# FPGA.net
KiCad netlist of a schematic drawn in Altium Designer
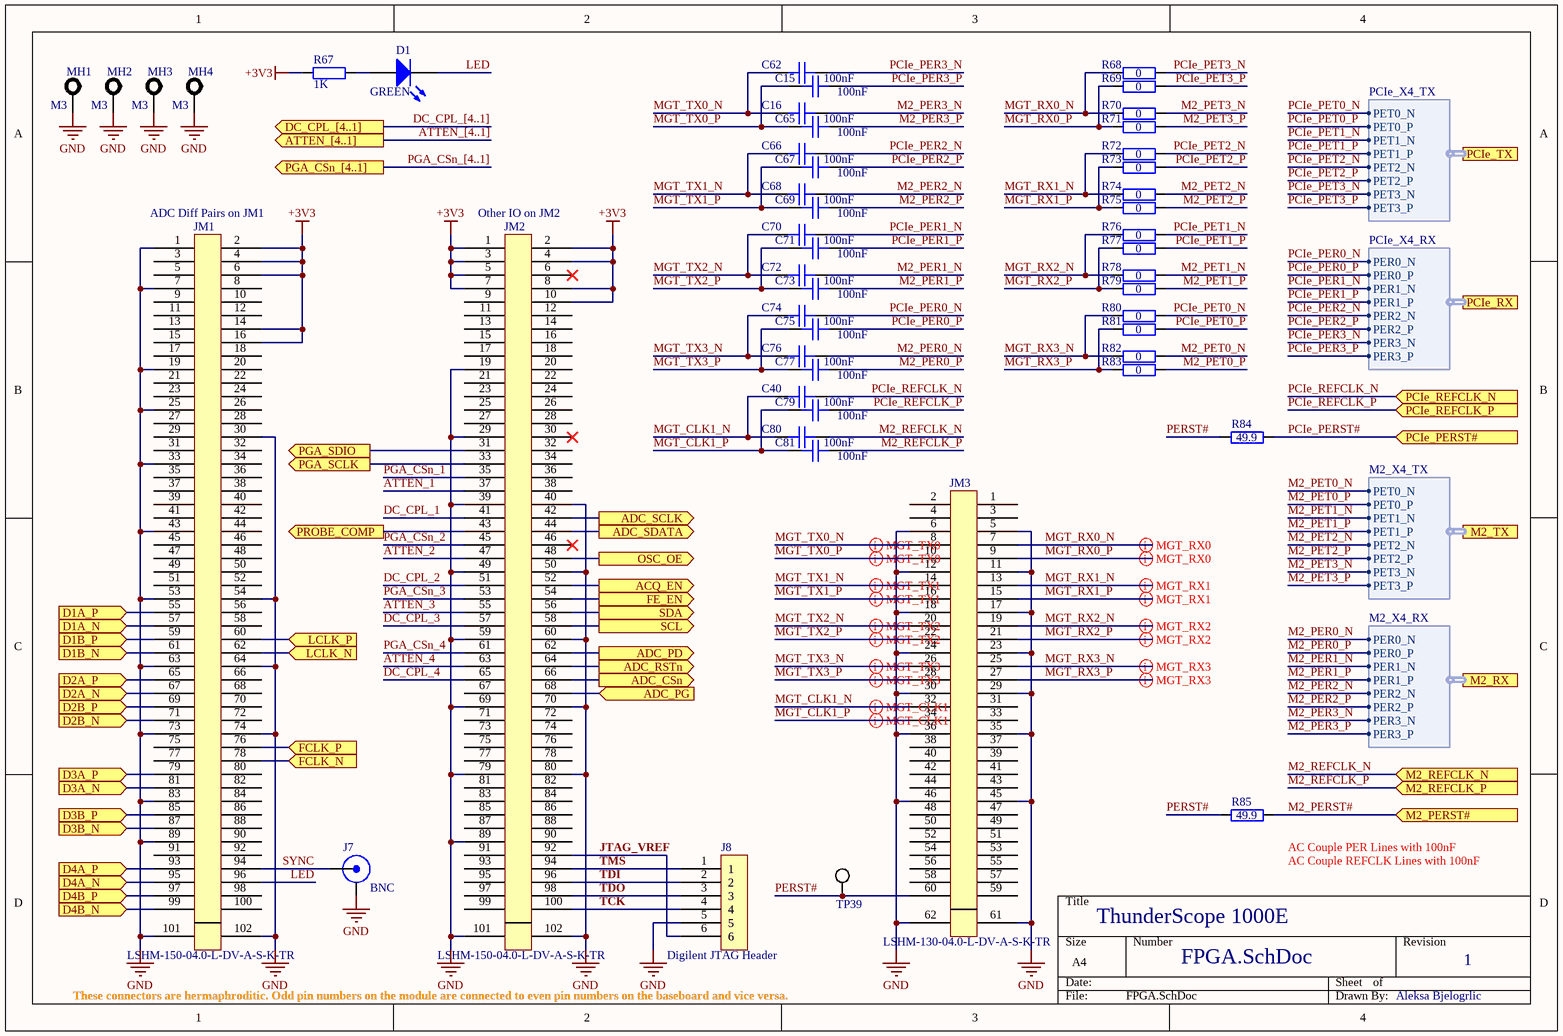
[diagram p0: FPGA.SchDoc]

(export (version "E")
  (design (tool "Eeschema 10.0.6"))
  (components
    (comp (ref "C15")
      (value "100nF")
      (footprint "GEN_C_0201")
      (libsource (lib "DSO") (part "CAP 100nF 6.3V X5R 0201"))
    )
    (comp (ref "C16")
      (value "100nF")
      (footprint "GEN_C_0201")
      (libsource (lib "DSO") (part "CAP 100nF 6.3V X5R 0201"))
    )
    (comp (ref "C40")
      (value "100nF")
      (footprint "GEN_C_0201")
      (libsource (lib "DSO") (part "CAP 100nF 6.3V X5R 0201"))
    )
    (comp (ref "C62")
      (value "100nF")
      (footprint "GEN_C_0201")
      (libsource (lib "DSO") (part "CAP 100nF 6.3V X5R 0201"))
    )
    (comp (ref "C65")
      (value "100nF")
      (footprint "GEN_C_0201")
      (libsource (lib "DSO") (part "CAP 100nF 6.3V X5R 0201"))
    )
    (comp (ref "C66")
      (value "100nF")
      (footprint "GEN_C_0201")
      (libsource (lib "DSO") (part "CAP 100nF 6.3V X5R 0201"))
    )
    (comp (ref "C67")
      (value "100nF")
      (footprint "GEN_C_0201")
      (libsource (lib "DSO") (part "CAP 100nF 6.3V X5R 0201"))
    )
    (comp (ref "C68")
      (value "100nF")
      (footprint "GEN_C_0201")
      (libsource (lib "DSO") (part "CAP 100nF 6.3V X5R 0201"))
    )
    (comp (ref "C69")
      (value "100nF")
      (footprint "GEN_C_0201")
      (libsource (lib "DSO") (part "CAP 100nF 6.3V X5R 0201"))
    )
    (comp (ref "C70")
      (value "100nF")
      (footprint "GEN_C_0201")
      (libsource (lib "DSO") (part "CAP 100nF 6.3V X5R 0201"))
    )
    (comp (ref "C71")
      (value "100nF")
      (footprint "GEN_C_0201")
      (libsource (lib "DSO") (part "CAP 100nF 6.3V X5R 0201"))
    )
    (comp (ref "C72")
      (value "100nF")
      (footprint "GEN_C_0201")
      (libsource (lib "DSO") (part "CAP 100nF 6.3V X5R 0201"))
    )
    (comp (ref "C73")
      (value "100nF")
      (footprint "GEN_C_0201")
      (libsource (lib "DSO") (part "CAP 100nF 6.3V X5R 0201"))
    )
    (comp (ref "C74")
      (value "100nF")
      (footprint "GEN_C_0201")
      (libsource (lib "DSO") (part "CAP 100nF 6.3V X5R 0201"))
    )
    (comp (ref "C75")
      (value "100nF")
      (footprint "GEN_C_0201")
      (libsource (lib "DSO") (part "CAP 100nF 6.3V X5R 0201"))
    )
    (comp (ref "C76")
      (value "100nF")
      (footprint "GEN_C_0201")
      (libsource (lib "DSO") (part "CAP 100nF 6.3V X5R 0201"))
    )
    (comp (ref "C77")
      (value "100nF")
      (footprint "GEN_C_0201")
      (libsource (lib "DSO") (part "CAP 100nF 6.3V X5R 0201"))
    )
    (comp (ref "C79")
      (value "100nF")
      (footprint "GEN_C_0201")
      (libsource (lib "DSO") (part "CAP 100nF 6.3V X5R 0201"))
    )
    (comp (ref "C80")
      (value "100nF")
      (footprint "GEN_C_0201")
      (libsource (lib "DSO") (part "CAP 100nF 6.3V X5R 0201"))
    )
    (comp (ref "C81")
      (value "100nF")
      (footprint "GEN_C_0201")
      (libsource (lib "DSO") (part "CAP 100nF 6.3V X5R 0201"))
    )
    (comp (ref "D1")
      (value "GREEN")
      (footprint "LED_0603_APT1608")
      (libsource (lib "DSO") (part "LED GREEN 0603 APT1608"))
    )
    (comp (ref "J7") (value "BNC") (footprint "MOL_0731000105") (libsource (lib "DSO") (part "BNC JACK R/A")))
    (comp (ref "J8")
      (value "2.54mm 6 Pin TH")
      (footprint "GEN_2.54mm_6_Pin_TH_RA")
      (libsource (lib "DSO") (part "CONN 2.54mm 6 Pin TH RA"))
    )
    (comp (ref "JM1")
      (value "LSHM-150-04.0-L-DV-A-S-K-TR")
      (footprint "SAM_LSHM-150-XX.X-XX-DV-A-S")
      (libsource (lib "DSO") (part "CONN LSHM-150-04.0-L-DV-A-S-K-TR"))
    )
    (comp (ref "JM2")
      (value "LSHM-150-04.0-L-DV-A-S-K-TR")
      (footprint "SAM_LSHM-150-XX.X-XX-DV-A-S")
      (libsource (lib "DSO") (part "CONN LSHM-150-04.0-L-DV-A-S-K-TR"))
    )
    (comp (ref "JM3")
      (value "LSHM-130-04.0-L-DV-A-S-K-TR")
      (footprint "SAM_LSHM-130-XX.X-XX-DV-A-S")
      (libsource (lib "DSO") (part "CONN LSHM-130-04.0-L-DV-A-S-K-TR"))
    )
    (comp (ref "MH1") (value "M3") (footprint "MH M3") (libsource (lib "DSO") (part "MH M3")))
    (comp (ref "MH2") (value "M3") (footprint "MH M3") (libsource (lib "DSO") (part "MH M3")))
    (comp (ref "MH3") (value "M3") (footprint "MH M3") (libsource (lib "DSO") (part "MH M3")))
    (comp (ref "MH4") (value "M3") (footprint "MH M3") (libsource (lib "DSO") (part "MH M3")))
    (comp (ref "R67")
      (value "1K")
      (footprint "GEN_R_0402")
      (fields (field (name "TOLERANCE") "1%"))
      (libsource (lib "DSO") (part "RES 1K OHM 1% 1/10W 0402"))
    )
    (comp (ref "R68")
      (value "0")
      (footprint "GEN_R_0201")
      (fields (field (name "TOLERANCE") "1%"))
      (libsource (lib "DSO") (part "RES 0 OHM 1% 1/20W 0201"))
    )
    (comp (ref "R69")
      (value "0")
      (footprint "GEN_R_0201")
      (fields (field (name "TOLERANCE") "1%"))
      (libsource (lib "DSO") (part "RES 0 OHM 1% 1/20W 0201"))
    )
    (comp (ref "R70")
      (value "0")
      (footprint "GEN_R_0201")
      (fields (field (name "TOLERANCE") "1%"))
      (libsource (lib "DSO") (part "RES 0 OHM 1% 1/20W 0201"))
    )
    (comp (ref "R71")
      (value "0")
      (footprint "GEN_R_0201")
      (fields (field (name "TOLERANCE") "1%"))
      (libsource (lib "DSO") (part "RES 0 OHM 1% 1/20W 0201"))
    )
    (comp (ref "R72")
      (value "0")
      (footprint "GEN_R_0201")
      (fields (field (name "TOLERANCE") "1%"))
      (libsource (lib "DSO") (part "RES 0 OHM 1% 1/20W 0201"))
    )
    (comp (ref "R73")
      (value "0")
      (footprint "GEN_R_0201")
      (fields (field (name "TOLERANCE") "1%"))
      (libsource (lib "DSO") (part "RES 0 OHM 1% 1/20W 0201"))
    )
    (comp (ref "R74")
      (value "0")
      (footprint "GEN_R_0201")
      (fields (field (name "TOLERANCE") "1%"))
      (libsource (lib "DSO") (part "RES 0 OHM 1% 1/20W 0201"))
    )
    (comp (ref "R75")
      (value "0")
      (footprint "GEN_R_0201")
      (fields (field (name "TOLERANCE") "1%"))
      (libsource (lib "DSO") (part "RES 0 OHM 1% 1/20W 0201"))
    )
    (comp (ref "R76")
      (value "0")
      (footprint "GEN_R_0201")
      (fields (field (name "TOLERANCE") "1%"))
      (libsource (lib "DSO") (part "RES 0 OHM 1% 1/20W 0201"))
    )
    (comp (ref "R77")
      (value "0")
      (footprint "GEN_R_0201")
      (fields (field (name "TOLERANCE") "1%"))
      (libsource (lib "DSO") (part "RES 0 OHM 1% 1/20W 0201"))
    )
    (comp (ref "R78")
      (value "0")
      (footprint "GEN_R_0201")
      (fields (field (name "TOLERANCE") "1%"))
      (libsource (lib "DSO") (part "RES 0 OHM 1% 1/20W 0201"))
    )
    (comp (ref "R79")
      (value "0")
      (footprint "GEN_R_0201")
      (fields (field (name "TOLERANCE") "1%"))
      (libsource (lib "DSO") (part "RES 0 OHM 1% 1/20W 0201"))
    )
    (comp (ref "R80")
      (value "0")
      (footprint "GEN_R_0201")
      (fields (field (name "TOLERANCE") "1%"))
      (libsource (lib "DSO") (part "RES 0 OHM 1% 1/20W 0201"))
    )
    (comp (ref "R81")
      (value "0")
      (footprint "GEN_R_0201")
      (fields (field (name "TOLERANCE") "1%"))
      (libsource (lib "DSO") (part "RES 0 OHM 1% 1/20W 0201"))
    )
    (comp (ref "R82")
      (value "0")
      (footprint "GEN_R_0201")
      (fields (field (name "TOLERANCE") "1%"))
      (libsource (lib "DSO") (part "RES 0 OHM 1% 1/20W 0201"))
    )
    (comp (ref "R83")
      (value "0")
      (footprint "GEN_R_0201")
      (fields (field (name "TOLERANCE") "1%"))
      (libsource (lib "DSO") (part "RES 0 OHM 1% 1/20W 0201"))
    )
    (comp (ref "R84")
      (value "49.9")
      (footprint "GEN_R_0402")
      (fields (field (name "TOLERANCE") "1%"))
      (libsource (lib "DSO") (part "RES 49.9 OHM 1% 1/10W 0402"))
    )
    (comp (ref "R85")
      (value "49.9")
      (footprint "GEN_R_0402")
      (fields (field (name "TOLERANCE") "1%"))
      (libsource (lib "DSO") (part "RES 49.9 OHM 1% 1/10W 0402"))
    )
    (comp (ref "TP39") (value "PCB") (footprint "GEN_TP_PCB") (libsource (lib "DSO") (part "TP PCB 1mm")))
  )
  (nets
    (net (code "5") (name "+3V3") (class "Default")
      (node (ref "JM1") (pin "14") (pinfunction "14_14") (pintype "passive"))
      (node (ref "JM1") (pin "16") (pinfunction "16_16") (pintype "passive"))
      (node (ref "JM1") (pin "2") (pinfunction "2_2") (pintype "passive"))
      (node (ref "JM1") (pin "4") (pinfunction "4_4") (pintype "passive"))
      (node (ref "JM1") (pin "6") (pinfunction "6_6") (pintype "passive"))
      (node (ref "JM2") (pin "1") (pinfunction "1_1") (pintype "passive"))
      (node (ref "JM2") (pin "10") (pinfunction "10_10") (pintype "passive"))
      (node (ref "JM2") (pin "2") (pinfunction "2_2") (pintype "passive"))
      (node (ref "JM2") (pin "3") (pinfunction "3_3") (pintype "passive"))
      (node (ref "JM2") (pin "4") (pinfunction "4_4") (pintype "passive"))
      (node (ref "JM2") (pin "5") (pinfunction "5_5") (pintype "passive"))
      (node (ref "JM2") (pin "7") (pinfunction "7_7") (pintype "passive"))
      (node (ref "JM2") (pin "8") (pinfunction "8_8") (pintype "passive"))
      (node (ref "R67") (pin "2") (pinfunction "2_2") (pintype "passive"))
    )
    (net (code "6") (name "/ACQ_EN") (class "Default")
      (node (ref "JM2") (pin "52") (pinfunction "52_52") (pintype "passive"))
    )
    (net (code "7") (name "/ADC_CSn") (class "Default")
      (node (ref "JM2") (pin "66") (pinfunction "66_66") (pintype "passive"))
    )
    (net (code "8") (name "/ADC_PD") (class "Default")
      (node (ref "JM2") (pin "62") (pinfunction "62_62") (pintype "passive"))
    )
    (net (code "9") (name "/ADC_PG") (class "Default")
      (node (ref "JM2") (pin "68") (pinfunction "68_68") (pintype "passive"))
    )
    (net (code "10") (name "/ADC_RSTn") (class "Default")
      (node (ref "JM2") (pin "64") (pinfunction "64_64") (pintype "passive"))
    )
    (net (code "11") (name "/ADC_SCLK") (class "Default")
      (node (ref "JM2") (pin "42") (pinfunction "42_42") (pintype "passive"))
    )
    (net (code "12") (name "/ADC_SDATA") (class "Default")
      (node (ref "JM2") (pin "44") (pinfunction "44_44") (pintype "passive"))
    )
    (net (code "13") (name "/ATTEN_1") (class "Default")
      (node (ref "JM2") (pin "37") (pinfunction "37_37") (pintype "passive"))
    )
    (net (code "14") (name "/ATTEN_2") (class "Default")
      (node (ref "JM2") (pin "47") (pinfunction "47_47") (pintype "passive"))
    )
    (net (code "15") (name "/ATTEN_3") (class "Default")
      (node (ref "JM2") (pin "55") (pinfunction "55_55") (pintype "passive"))
    )
    (net (code "16") (name "/ATTEN_4") (class "Default")
      (node (ref "JM2") (pin "63") (pinfunction "63_63") (pintype "passive"))
    )
    (net (code "18") (name "/D1A_N") (class "Default")
      (node (ref "JM1") (pin "57") (pinfunction "57_57") (pintype "passive"))
    )
    (net (code "19") (name "/D1A_P") (class "Default")
      (node (ref "JM1") (pin "55") (pinfunction "55_55") (pintype "passive"))
    )
    (net (code "20") (name "/D1B_N") (class "Default")
      (node (ref "JM1") (pin "61") (pinfunction "61_61") (pintype "passive"))
    )
    (net (code "21") (name "/D1B_P") (class "Default")
      (node (ref "JM1") (pin "59") (pinfunction "59_59") (pintype "passive"))
    )
    (net (code "22") (name "/D2A_N") (class "Default")
      (node (ref "JM1") (pin "67") (pinfunction "67_67") (pintype "passive"))
    )
    (net (code "23") (name "/D2A_P") (class "Default")
      (node (ref "JM1") (pin "65") (pinfunction "65_65") (pintype "passive"))
    )
    (net (code "24") (name "/D2B_N") (class "Default")
      (node (ref "JM1") (pin "71") (pinfunction "71_71") (pintype "passive"))
    )
    (net (code "25") (name "/D2B_P") (class "Default")
      (node (ref "JM1") (pin "69") (pinfunction "69_69") (pintype "passive"))
    )
    (net (code "26") (name "/D3A_N") (class "Default")
      (node (ref "JM1") (pin "81") (pinfunction "81_81") (pintype "passive"))
    )
    (net (code "27") (name "/D3A_P") (class "Default")
      (node (ref "JM1") (pin "79") (pinfunction "79_79") (pintype "passive"))
    )
    (net (code "28") (name "/D3B_N") (class "Default")
      (node (ref "JM1") (pin "87") (pinfunction "87_87") (pintype "passive"))
    )
    (net (code "29") (name "/D3B_P") (class "Default")
      (node (ref "JM1") (pin "85") (pinfunction "85_85") (pintype "passive"))
    )
    (net (code "30") (name "/D4A_N") (class "Default")
      (node (ref "JM1") (pin "95") (pinfunction "95_95") (pintype "passive"))
    )
    (net (code "31") (name "/D4A_P") (class "Default")
      (node (ref "JM1") (pin "93") (pinfunction "93_93") (pintype "passive"))
    )
    (net (code "32") (name "/D4B_N") (class "Default")
      (node (ref "JM1") (pin "99") (pinfunction "99_99") (pintype "passive"))
    )
    (net (code "33") (name "/D4B_P") (class "Default")
      (node (ref "JM1") (pin "97") (pinfunction "97_97") (pintype "passive"))
    )
    (net (code "34") (name "/DC_CPL_1") (class "Default")
      (node (ref "JM2") (pin "41") (pinfunction "41_41") (pintype "passive"))
    )
    (net (code "35") (name "/DC_CPL_2") (class "Default")
      (node (ref "JM2") (pin "51") (pinfunction "51_51") (pintype "passive"))
    )
    (net (code "36") (name "/DC_CPL_3") (class "Default")
      (node (ref "JM2") (pin "57") (pinfunction "57_57") (pintype "passive"))
    )
    (net (code "37") (name "/DC_CPL_4") (class "Default")
      (node (ref "JM2") (pin "65") (pinfunction "65_65") (pintype "passive"))
    )
    (net (code "39") (name "/FCLK_N") (class "Default")
      (node (ref "JM1") (pin "78") (pinfunction "78_78") (pintype "passive"))
    )
    (net (code "40") (name "/FCLK_P") (class "Default")
      (node (ref "JM1") (pin "76") (pinfunction "76_76") (pintype "passive"))
    )
    (net (code "41") (name "/FE_EN") (class "Default")
      (node (ref "JM2") (pin "54") (pinfunction "54_54") (pintype "passive"))
    )
    (net (code "42") (name "/JTAG_VREF") (class "Default")
      (node (ref "J8") (pin "6") (pinfunction "6_6") (pintype "passive"))
      (node (ref "JM2") (pin "92") (pinfunction "92_92") (pintype "passive"))
    )
    (net (code "43") (name "/LCLK_N") (class "Default")
      (node (ref "JM1") (pin "62") (pinfunction "62_62") (pintype "passive"))
    )
    (net (code "44") (name "/LCLK_P") (class "Default")
      (node (ref "JM1") (pin "60") (pinfunction "60_60") (pintype "passive"))
    )
    (net (code "45") (name "/LED") (class "Default")
      (node (ref "D1") (pin "1") (pinfunction "K_1") (pintype "passive"))
      (node (ref "JM1") (pin "96") (pinfunction "96_96") (pintype "passive"))
    )
    (net (code "46") (name "/M2_PER0_N") (class "Default")
      (node (ref "C76") (pin "1") (pinfunction "1_1") (pintype "passive"))
    )
    (net (code "47") (name "/M2_PER0_P") (class "Default")
      (node (ref "C77") (pin "1") (pinfunction "1_1") (pintype "passive"))
    )
    (net (code "48") (name "/M2_PER1_N") (class "Default")
      (node (ref "C72") (pin "1") (pinfunction "1_1") (pintype "passive"))
    )
    (net (code "49") (name "/M2_PER1_P") (class "Default")
      (node (ref "C73") (pin "1") (pinfunction "1_1") (pintype "passive"))
    )
    (net (code "50") (name "/M2_PER2_N") (class "Default")
      (node (ref "C68") (pin "1") (pinfunction "1_1") (pintype "passive"))
    )
    (net (code "51") (name "/M2_PER2_P") (class "Default")
      (node (ref "C69") (pin "1") (pinfunction "1_1") (pintype "passive"))
    )
    (net (code "52") (name "/M2_PER3_N") (class "Default")
      (node (ref "C16") (pin "1") (pinfunction "1_1") (pintype "passive"))
    )
    (net (code "53") (name "/M2_PER3_P") (class "Default")
      (node (ref "C65") (pin "1") (pinfunction "1_1") (pintype "passive"))
    )
    (net (code "54") (name "/M2_PERST#") (class "Default")
      (node (ref "R85") (pin "2") (pinfunction "2_2") (pintype "passive"))
    )
    (net (code "55") (name "/M2_PET0_N") (class "Default")
      (node (ref "R82") (pin "2") (pinfunction "2_2") (pintype "passive"))
    )
    (net (code "56") (name "/M2_PET0_P") (class "Default")
      (node (ref "R83") (pin "2") (pinfunction "2_2") (pintype "passive"))
    )
    (net (code "57") (name "/M2_PET1_N") (class "Default")
      (node (ref "R78") (pin "2") (pinfunction "2_2") (pintype "passive"))
    )
    (net (code "58") (name "/M2_PET1_P") (class "Default")
      (node (ref "R79") (pin "2") (pinfunction "2_2") (pintype "passive"))
    )
    (net (code "59") (name "/M2_PET2_N") (class "Default")
      (node (ref "R74") (pin "2") (pinfunction "2_2") (pintype "passive"))
    )
    (net (code "60") (name "/M2_PET2_P") (class "Default")
      (node (ref "R75") (pin "2") (pinfunction "2_2") (pintype "passive"))
    )
    (net (code "61") (name "/M2_PET3_N") (class "Default")
      (node (ref "R70") (pin "2") (pinfunction "2_2") (pintype "passive"))
    )
    (net (code "62") (name "/M2_PET3_P") (class "Default")
      (node (ref "R71") (pin "2") (pinfunction "2_2") (pintype "passive"))
    )
    (net (code "63") (name "/M2_REFCLK_N") (class "Default")
      (node (ref "C80") (pin "1") (pinfunction "1_1") (pintype "passive"))
    )
    (net (code "64") (name "/M2_REFCLK_P") (class "Default")
      (node (ref "C81") (pin "1") (pinfunction "1_1") (pintype "passive"))
    )
    (net (code "65") (name "/MGT_CLK1_N") (class "Default")
      (node (ref "C40") (pin "2") (pinfunction "2_2") (pintype "passive"))
      (node (ref "C80") (pin "2") (pinfunction "2_2") (pintype "passive"))
      (node (ref "JM3") (pin "32") (pinfunction "32_32") (pintype "passive"))
    )
    (net (code "66") (name "/MGT_CLK1_P") (class "Default")
      (node (ref "C79") (pin "2") (pinfunction "2_2") (pintype "passive"))
      (node (ref "C81") (pin "2") (pinfunction "2_2") (pintype "passive"))
      (node (ref "JM3") (pin "34") (pinfunction "34_34") (pintype "passive"))
    )
    (net (code "67") (name "/MGT_RX0_N") (class "Default")
      (node (ref "JM3") (pin "7") (pinfunction "7_7") (pintype "passive"))
      (node (ref "R68") (pin "1") (pinfunction "1_1") (pintype "passive"))
      (node (ref "R70") (pin "1") (pinfunction "1_1") (pintype "passive"))
    )
    (net (code "68") (name "/MGT_RX0_P") (class "Default")
      (node (ref "JM3") (pin "9") (pinfunction "9_9") (pintype "passive"))
      (node (ref "R69") (pin "1") (pinfunction "1_1") (pintype "passive"))
      (node (ref "R71") (pin "1") (pinfunction "1_1") (pintype "passive"))
    )
    (net (code "69") (name "/MGT_RX1_N") (class "Default")
      (node (ref "JM3") (pin "13") (pinfunction "13_13") (pintype "passive"))
      (node (ref "R72") (pin "1") (pinfunction "1_1") (pintype "passive"))
      (node (ref "R74") (pin "1") (pinfunction "1_1") (pintype "passive"))
    )
    (net (code "70") (name "/MGT_RX1_P") (class "Default")
      (node (ref "JM3") (pin "15") (pinfunction "15_15") (pintype "passive"))
      (node (ref "R73") (pin "1") (pinfunction "1_1") (pintype "passive"))
      (node (ref "R75") (pin "1") (pinfunction "1_1") (pintype "passive"))
    )
    (net (code "71") (name "/MGT_RX2_N") (class "Default")
      (node (ref "JM3") (pin "19") (pinfunction "19_19") (pintype "passive"))
      (node (ref "R76") (pin "1") (pinfunction "1_1") (pintype "passive"))
      (node (ref "R78") (pin "1") (pinfunction "1_1") (pintype "passive"))
    )
    (net (code "72") (name "/MGT_RX2_P") (class "Default")
      (node (ref "JM3") (pin "21") (pinfunction "21_21") (pintype "passive"))
      (node (ref "R77") (pin "1") (pinfunction "1_1") (pintype "passive"))
      (node (ref "R79") (pin "1") (pinfunction "1_1") (pintype "passive"))
    )
    (net (code "73") (name "/MGT_RX3_N") (class "Default")
      (node (ref "JM3") (pin "25") (pinfunction "25_25") (pintype "passive"))
      (node (ref "R80") (pin "1") (pinfunction "1_1") (pintype "passive"))
      (node (ref "R82") (pin "1") (pinfunction "1_1") (pintype "passive"))
    )
    (net (code "74") (name "/MGT_RX3_P") (class "Default")
      (node (ref "JM3") (pin "27") (pinfunction "27_27") (pintype "passive"))
      (node (ref "R81") (pin "1") (pinfunction "1_1") (pintype "passive"))
      (node (ref "R83") (pin "1") (pinfunction "1_1") (pintype "passive"))
    )
    (net (code "75") (name "/MGT_TX0_N") (class "Default")
      (node (ref "C16") (pin "2") (pinfunction "2_2") (pintype "passive"))
      (node (ref "C62") (pin "2") (pinfunction "2_2") (pintype "passive"))
      (node (ref "JM3") (pin "8") (pinfunction "8_8") (pintype "passive"))
    )
    (net (code "76") (name "/MGT_TX0_P") (class "Default")
      (node (ref "C15") (pin "2") (pinfunction "2_2") (pintype "passive"))
      (node (ref "C65") (pin "2") (pinfunction "2_2") (pintype "passive"))
      (node (ref "JM3") (pin "10") (pinfunction "10_10") (pintype "passive"))
    )
    (net (code "77") (name "/MGT_TX1_N") (class "Default")
      (node (ref "C66") (pin "2") (pinfunction "2_2") (pintype "passive"))
      (node (ref "C68") (pin "2") (pinfunction "2_2") (pintype "passive"))
      (node (ref "JM3") (pin "14") (pinfunction "14_14") (pintype "passive"))
    )
    (net (code "78") (name "/MGT_TX1_P") (class "Default")
      (node (ref "C67") (pin "2") (pinfunction "2_2") (pintype "passive"))
      (node (ref "C69") (pin "2") (pinfunction "2_2") (pintype "passive"))
      (node (ref "JM3") (pin "16") (pinfunction "16_16") (pintype "passive"))
    )
    (net (code "79") (name "/MGT_TX2_N") (class "Default")
      (node (ref "C70") (pin "2") (pinfunction "2_2") (pintype "passive"))
      (node (ref "C72") (pin "2") (pinfunction "2_2") (pintype "passive"))
      (node (ref "JM3") (pin "20") (pinfunction "20_20") (pintype "passive"))
    )
    (net (code "80") (name "/MGT_TX2_P") (class "Default")
      (node (ref "C71") (pin "2") (pinfunction "2_2") (pintype "passive"))
      (node (ref "C73") (pin "2") (pinfunction "2_2") (pintype "passive"))
      (node (ref "JM3") (pin "22") (pinfunction "22_22") (pintype "passive"))
    )
    (net (code "81") (name "/MGT_TX3_N") (class "Default")
      (node (ref "C74") (pin "2") (pinfunction "2_2") (pintype "passive"))
      (node (ref "C76") (pin "2") (pinfunction "2_2") (pintype "passive"))
      (node (ref "JM3") (pin "26") (pinfunction "26_26") (pintype "passive"))
    )
    (net (code "82") (name "/MGT_TX3_P") (class "Default")
      (node (ref "C75") (pin "2") (pinfunction "2_2") (pintype "passive"))
      (node (ref "C77") (pin "2") (pinfunction "2_2") (pintype "passive"))
      (node (ref "JM3") (pin "28") (pinfunction "28_28") (pintype "passive"))
    )
    (net (code "83") (name "/OSC_OE") (class "Default")
      (node (ref "JM2") (pin "48") (pinfunction "48_48") (pintype "passive"))
    )
    (net (code "84") (name "/PCIe_PER0_N") (class "Default")
      (node (ref "C74") (pin "1") (pinfunction "1_1") (pintype "passive"))
    )
    (net (code "85") (name "/PCIe_PER0_P") (class "Default")
      (node (ref "C75") (pin "1") (pinfunction "1_1") (pintype "passive"))
    )
    (net (code "86") (name "/PCIe_PER1_N") (class "Default")
      (node (ref "C70") (pin "1") (pinfunction "1_1") (pintype "passive"))
    )
    (net (code "87") (name "/PCIe_PER1_P") (class "Default")
      (node (ref "C71") (pin "1") (pinfunction "1_1") (pintype "passive"))
    )
    (net (code "88") (name "/PCIe_PER2_N") (class "Default")
      (node (ref "C66") (pin "1") (pinfunction "1_1") (pintype "passive"))
    )
    (net (code "89") (name "/PCIe_PER2_P") (class "Default")
      (node (ref "C67") (pin "1") (pinfunction "1_1") (pintype "passive"))
    )
    (net (code "90") (name "/PCIe_PER3_N") (class "Default")
      (node (ref "C62") (pin "1") (pinfunction "1_1") (pintype "passive"))
    )
    (net (code "91") (name "/PCIe_PER3_P") (class "Default")
      (node (ref "C15") (pin "1") (pinfunction "1_1") (pintype "passive"))
    )
    (net (code "92") (name "/PCIe_PERST#") (class "Default")
      (node (ref "R84") (pin "2") (pinfunction "2_2") (pintype "passive"))
    )
    (net (code "93") (name "/PCIe_PET0_N") (class "Default")
      (node (ref "R80") (pin "2") (pinfunction "2_2") (pintype "passive"))
    )
    (net (code "94") (name "/PCIe_PET0_P") (class "Default")
      (node (ref "R81") (pin "2") (pinfunction "2_2") (pintype "passive"))
    )
    (net (code "95") (name "/PCIe_PET1_N") (class "Default")
      (node (ref "R76") (pin "2") (pinfunction "2_2") (pintype "passive"))
    )
    (net (code "96") (name "/PCIe_PET1_P") (class "Default")
      (node (ref "R77") (pin "2") (pinfunction "2_2") (pintype "passive"))
    )
    (net (code "97") (name "/PCIe_PET2_N") (class "Default")
      (node (ref "R72") (pin "2") (pinfunction "2_2") (pintype "passive"))
    )
    (net (code "98") (name "/PCIe_PET2_P") (class "Default")
      (node (ref "R73") (pin "2") (pinfunction "2_2") (pintype "passive"))
    )
    (net (code "99") (name "/PCIe_PET3_N") (class "Default")
      (node (ref "R68") (pin "2") (pinfunction "2_2") (pintype "passive"))
    )
    (net (code "100") (name "/PCIe_PET3_P") (class "Default")
      (node (ref "R69") (pin "2") (pinfunction "2_2") (pintype "passive"))
    )
    (net (code "101") (name "/PCIe_REFCLK_N") (class "Default")
      (node (ref "C40") (pin "1") (pinfunction "1_1") (pintype "passive"))
    )
    (net (code "102") (name "/PCIe_REFCLK_P") (class "Default")
      (node (ref "C79") (pin "1") (pinfunction "1_1") (pintype "passive"))
    )
    (net (code "103") (name "/PERST#") (class "Default")
      (node (ref "JM3") (pin "60") (pinfunction "60_60") (pintype "passive"))
      (node (ref "R84") (pin "1") (pinfunction "1_1") (pintype "passive"))
      (node (ref "R85") (pin "1") (pinfunction "1_1") (pintype "passive"))
      (node (ref "TP39") (pin "1") (pinfunction "1_1") (pintype "passive"))
    )
    (net (code "104") (name "/PGA_CSn_1") (class "Default")
      (node (ref "JM2") (pin "35") (pinfunction "35_35") (pintype "passive"))
    )
    (net (code "105") (name "/PGA_CSn_2") (class "Default")
      (node (ref "JM2") (pin "45") (pinfunction "45_45") (pintype "passive"))
    )
    (net (code "106") (name "/PGA_CSn_3") (class "Default")
      (node (ref "JM2") (pin "53") (pinfunction "53_53") (pintype "passive"))
    )
    (net (code "107") (name "/PGA_CSn_4") (class "Default")
      (node (ref "JM2") (pin "61") (pinfunction "61_61") (pintype "passive"))
    )
    (net (code "109") (name "/PGA_SCLK") (class "Default")
      (node (ref "JM2") (pin "33") (pinfunction "33_33") (pintype "passive"))
    )
    (net (code "110") (name "/PGA_SDIO") (class "Default")
      (node (ref "JM2") (pin "31") (pinfunction "31_31") (pintype "passive"))
    )
    (net (code "111") (name "/PROBE_COMP") (class "Default")
      (node (ref "JM2") (pin "43") (pinfunction "43_43") (pintype "passive"))
    )
    (net (code "112") (name "/SCL") (class "Default")
      (node (ref "JM2") (pin "58") (pinfunction "58_58") (pintype "passive"))
    )
    (net (code "113") (name "/SDA") (class "Default")
      (node (ref "JM2") (pin "56") (pinfunction "56_56") (pintype "passive"))
    )
    (net (code "114") (name "/SYNC") (class "Default")
      (node (ref "J7") (pin "1") (pinfunction "Signal_1") (pintype "passive"))
      (node (ref "JM1") (pin "94") (pinfunction "94_94") (pintype "passive"))
    )
    (net (code "115") (name "/TCK") (class "Default")
      (node (ref "J8") (pin "4") (pinfunction "4_4") (pintype "passive"))
      (node (ref "JM2") (pin "100") (pinfunction "100_100") (pintype "passive"))
    )
    (net (code "116") (name "/TDI") (class "Default")
      (node (ref "J8") (pin "2") (pinfunction "2_2") (pintype "passive"))
      (node (ref "JM2") (pin "96") (pinfunction "96_96") (pintype "passive"))
    )
    (net (code "117") (name "/TDO") (class "Default")
      (node (ref "J8") (pin "3") (pinfunction "3_3") (pintype "passive"))
      (node (ref "JM2") (pin "98") (pinfunction "98_98") (pintype "passive"))
    )
    (net (code "118") (name "/TMS") (class "Default")
      (node (ref "J8") (pin "1") (pinfunction "1_1") (pintype "passive"))
      (node (ref "JM2") (pin "94") (pinfunction "94_94") (pintype "passive"))
    )
    (net (code "123") (name "GND") (class "Default")
      (node (ref "J7") (pin "2") (pinfunction "SHIELD_2") (pintype "passive"))
      (node (ref "J8") (pin "5") (pinfunction "5_5") (pintype "passive"))
      (node (ref "JM1") (pin "1") (pinfunction "1_1") (pintype "passive"))
      (node (ref "JM1") (pin "101") (pinfunction "101_101") (pintype "passive"))
      (node (ref "JM1") (pin "102") (pinfunction "102_102") (pintype "passive"))
      (node (ref "JM1") (pin "19") (pinfunction "19_19") (pintype "passive"))
      (node (ref "JM1") (pin "25") (pinfunction "25_25") (pintype "passive"))
      (node (ref "JM1") (pin "30") (pinfunction "30_30") (pintype "passive"))
      (node (ref "JM1") (pin "33") (pinfunction "33_33") (pintype "passive"))
      (node (ref "JM1") (pin "43") (pinfunction "43_43") (pintype "passive"))
      (node (ref "JM1") (pin "53") (pinfunction "53_53") (pintype "passive"))
      (node (ref "JM1") (pin "54") (pinfunction "54_54") (pintype "passive"))
      (node (ref "JM1") (pin "63") (pinfunction "63_63") (pintype "passive"))
      (node (ref "JM1") (pin "64") (pinfunction "64_64") (pintype "passive"))
      (node (ref "JM1") (pin "7") (pinfunction "7_7") (pintype "passive"))
      (node (ref "JM1") (pin "73") (pinfunction "73_73") (pintype "passive"))
      (node (ref "JM1") (pin "74") (pinfunction "74_74") (pintype "passive"))
      (node (ref "JM1") (pin "83") (pinfunction "83_83") (pintype "passive"))
      (node (ref "JM1") (pin "89") (pinfunction "89_89") (pintype "passive"))
      (node (ref "JM2") (pin "101") (pinfunction "101_101") (pintype "passive"))
      (node (ref "JM2") (pin "102") (pinfunction "102_102") (pintype "passive"))
      (node (ref "JM2") (pin "19") (pinfunction "19_19") (pintype "passive"))
      (node (ref "JM2") (pin "29") (pinfunction "29_29") (pintype "passive"))
      (node (ref "JM2") (pin "39") (pinfunction "39_39") (pintype "passive"))
      (node (ref "JM2") (pin "40") (pinfunction "40_40") (pintype "passive"))
      (node (ref "JM2") (pin "49") (pinfunction "49_49") (pintype "passive"))
      (node (ref "JM2") (pin "50") (pinfunction "50_50") (pintype "passive"))
      (node (ref "JM2") (pin "59") (pinfunction "59_59") (pintype "passive"))
      (node (ref "JM2") (pin "60") (pinfunction "60_60") (pintype "passive"))
      (node (ref "JM2") (pin "69") (pinfunction "69_69") (pintype "passive"))
      (node (ref "JM2") (pin "70") (pinfunction "70_70") (pintype "passive"))
      (node (ref "JM2") (pin "79") (pinfunction "79_79") (pintype "passive"))
      (node (ref "JM2") (pin "80") (pinfunction "80_80") (pintype "passive"))
      (node (ref "JM2") (pin "89") (pinfunction "89_89") (pintype "passive"))
      (node (ref "JM3") (pin "11") (pinfunction "11_11") (pintype "passive"))
      (node (ref "JM3") (pin "12") (pinfunction "12_12") (pintype "passive"))
      (node (ref "JM3") (pin "17") (pinfunction "17_17") (pintype "passive"))
      (node (ref "JM3") (pin "18") (pinfunction "18_18") (pintype "passive"))
      (node (ref "JM3") (pin "23") (pinfunction "23_23") (pintype "passive"))
      (node (ref "JM3") (pin "24") (pinfunction "24_24") (pintype "passive"))
      (node (ref "JM3") (pin "29") (pinfunction "29_29") (pintype "passive"))
      (node (ref "JM3") (pin "30") (pinfunction "30_30") (pintype "passive"))
      (node (ref "JM3") (pin "35") (pinfunction "35_35") (pintype "passive"))
      (node (ref "JM3") (pin "36") (pinfunction "36_36") (pintype "passive"))
      (node (ref "JM3") (pin "45") (pinfunction "45_45") (pintype "passive"))
      (node (ref "JM3") (pin "46") (pinfunction "46_46") (pintype "passive"))
      (node (ref "JM3") (pin "5") (pinfunction "5_5") (pintype "passive"))
      (node (ref "JM3") (pin "6") (pinfunction "6_6") (pintype "passive"))
      (node (ref "JM3") (pin "61") (pinfunction "61_61") (pintype "passive"))
      (node (ref "JM3") (pin "62") (pinfunction "62_62") (pintype "passive"))
      (node (ref "MH1") (pin "1") (pinfunction "1_1") (pintype "passive"))
      (node (ref "MH2") (pin "1") (pinfunction "1_1") (pintype "passive"))
      (node (ref "MH3") (pin "1") (pinfunction "1_1") (pintype "passive"))
      (node (ref "MH4") (pin "1") (pinfunction "1_1") (pintype "passive"))
    )
    (net (code "124") (name "Net-(D1-A)") (class "Default")
      (node (ref "D1") (pin "2") (pinfunction "A_2") (pintype "passive"))
      (node (ref "R67") (pin "1") (pinfunction "1_1") (pintype "passive"))
    )
    (net (code "125") (name "unconnected-(JM1-Pad3)") (class "Default")
      (node (ref "JM1") (pin "3") (pinfunction "3_3") (pintype "passive"))
    )
    (net (code "126") (name "unconnected-(JM1-Pad5)") (class "Default")
      (node (ref "JM1") (pin "5") (pinfunction "5_5") (pintype "passive"))
    )
    (net (code "127") (name "unconnected-(JM1-Pad8)") (class "Default")
      (node (ref "JM1") (pin "8") (pinfunction "8_8") (pintype "passive"))
    )
    (net (code "128") (name "unconnected-(JM1-Pad9)") (class "Default")
      (node (ref "JM1") (pin "9") (pinfunction "9_9") (pintype "passive"))
    )
    (net (code "129") (name "unconnected-(JM1-Pad10)") (class "Default")
      (node (ref "JM1") (pin "10") (pinfunction "10_10") (pintype "passive"))
    )
    (net (code "130") (name "unconnected-(JM1-Pad11)") (class "Default")
      (node (ref "JM1") (pin "11") (pinfunction "11_11") (pintype "passive"))
    )
    (net (code "131") (name "unconnected-(JM1-Pad12)") (class "Default")
      (node (ref "JM1") (pin "12") (pinfunction "12_12") (pintype "passive"))
    )
    (net (code "132") (name "unconnected-(JM1-Pad13)") (class "Default")
      (node (ref "JM1") (pin "13") (pinfunction "13_13") (pintype "passive"))
    )
    (net (code "133") (name "unconnected-(JM1-Pad15)") (class "Default")
      (node (ref "JM1") (pin "15") (pinfunction "15_15") (pintype "passive"))
    )
    (net (code "134") (name "unconnected-(JM1-Pad17)") (class "Default")
      (node (ref "JM1") (pin "17") (pinfunction "17_17") (pintype "passive"))
    )
    (net (code "135") (name "unconnected-(JM1-Pad18)") (class "Default")
      (node (ref "JM1") (pin "18") (pinfunction "18_18") (pintype "passive"))
    )
    (net (code "136") (name "unconnected-(JM1-Pad20)") (class "Default")
      (node (ref "JM1") (pin "20") (pinfunction "20_20") (pintype "passive"))
    )
    (net (code "137") (name "unconnected-(JM1-Pad21)") (class "Default")
      (node (ref "JM1") (pin "21") (pinfunction "21_21") (pintype "passive"))
    )
    (net (code "138") (name "unconnected-(JM1-Pad22)") (class "Default")
      (node (ref "JM1") (pin "22") (pinfunction "22_22") (pintype "passive"))
    )
    (net (code "139") (name "unconnected-(JM1-Pad23)") (class "Default")
      (node (ref "JM1") (pin "23") (pinfunction "23_23") (pintype "passive"))
    )
    (net (code "140") (name "unconnected-(JM1-Pad24)") (class "Default")
      (node (ref "JM1") (pin "24") (pinfunction "24_24") (pintype "passive"))
    )
    (net (code "141") (name "unconnected-(JM1-Pad26)") (class "Default")
      (node (ref "JM1") (pin "26") (pinfunction "26_26") (pintype "passive"))
    )
    (net (code "142") (name "unconnected-(JM1-Pad27)") (class "Default")
      (node (ref "JM1") (pin "27") (pinfunction "27_27") (pintype "passive"))
    )
    (net (code "143") (name "unconnected-(JM1-Pad28)") (class "Default")
      (node (ref "JM1") (pin "28") (pinfunction "28_28") (pintype "passive"))
    )
    (net (code "144") (name "unconnected-(JM1-Pad29)") (class "Default")
      (node (ref "JM1") (pin "29") (pinfunction "29_29") (pintype "passive"))
    )
    (net (code "145") (name "unconnected-(JM1-Pad31)") (class "Default")
      (node (ref "JM1") (pin "31") (pinfunction "31_31") (pintype "passive"))
    )
    (net (code "146") (name "unconnected-(JM1-Pad32)") (class "Default")
      (node (ref "JM1") (pin "32") (pinfunction "32_32") (pintype "passive"))
    )
    (net (code "147") (name "unconnected-(JM1-Pad34)") (class "Default")
      (node (ref "JM1") (pin "34") (pinfunction "34_34") (pintype "passive"))
    )
    (net (code "148") (name "unconnected-(JM1-Pad35)") (class "Default")
      (node (ref "JM1") (pin "35") (pinfunction "35_35") (pintype "passive"))
    )
    (net (code "149") (name "unconnected-(JM1-Pad36)") (class "Default")
      (node (ref "JM1") (pin "36") (pinfunction "36_36") (pintype "passive"))
    )
    (net (code "150") (name "unconnected-(JM1-Pad37)") (class "Default")
      (node (ref "JM1") (pin "37") (pinfunction "37_37") (pintype "passive"))
    )
    (net (code "151") (name "unconnected-(JM1-Pad38)") (class "Default")
      (node (ref "JM1") (pin "38") (pinfunction "38_38") (pintype "passive"))
    )
    (net (code "152") (name "unconnected-(JM1-Pad39)") (class "Default")
      (node (ref "JM1") (pin "39") (pinfunction "39_39") (pintype "passive"))
    )
    (net (code "153") (name "unconnected-(JM1-Pad40)") (class "Default")
      (node (ref "JM1") (pin "40") (pinfunction "40_40") (pintype "passive"))
    )
    (net (code "154") (name "unconnected-(JM1-Pad41)") (class "Default")
      (node (ref "JM1") (pin "41") (pinfunction "41_41") (pintype "passive"))
    )
    (net (code "155") (name "unconnected-(JM1-Pad42)") (class "Default")
      (node (ref "JM1") (pin "42") (pinfunction "42_42") (pintype "passive"))
    )
    (net (code "156") (name "unconnected-(JM1-Pad44)") (class "Default")
      (node (ref "JM1") (pin "44") (pinfunction "44_44") (pintype "passive"))
    )
    (net (code "157") (name "unconnected-(JM1-Pad45)") (class "Default")
      (node (ref "JM1") (pin "45") (pinfunction "45_45") (pintype "passive"))
    )
    (net (code "158") (name "unconnected-(JM1-Pad46)") (class "Default")
      (node (ref "JM1") (pin "46") (pinfunction "46_46") (pintype "passive"))
    )
    (net (code "159") (name "unconnected-(JM1-Pad47)") (class "Default")
      (node (ref "JM1") (pin "47") (pinfunction "47_47") (pintype "passive"))
    )
    (net (code "160") (name "unconnected-(JM1-Pad48)") (class "Default")
      (node (ref "JM1") (pin "48") (pinfunction "48_48") (pintype "passive"))
    )
    (net (code "161") (name "unconnected-(JM1-Pad49)") (class "Default")
      (node (ref "JM1") (pin "49") (pinfunction "49_49") (pintype "passive"))
    )
    (net (code "162") (name "unconnected-(JM1-Pad50)") (class "Default")
      (node (ref "JM1") (pin "50") (pinfunction "50_50") (pintype "passive"))
    )
    (net (code "163") (name "unconnected-(JM1-Pad51)") (class "Default")
      (node (ref "JM1") (pin "51") (pinfunction "51_51") (pintype "passive"))
    )
    (net (code "164") (name "unconnected-(JM1-Pad52)") (class "Default")
      (node (ref "JM1") (pin "52") (pinfunction "52_52") (pintype "passive"))
    )
    (net (code "165") (name "unconnected-(JM1-Pad56)") (class "Default")
      (node (ref "JM1") (pin "56") (pinfunction "56_56") (pintype "passive"))
    )
    (net (code "166") (name "unconnected-(JM1-Pad58)") (class "Default")
      (node (ref "JM1") (pin "58") (pinfunction "58_58") (pintype "passive"))
    )
    (net (code "167") (name "unconnected-(JM1-Pad66)") (class "Default")
      (node (ref "JM1") (pin "66") (pinfunction "66_66") (pintype "passive"))
    )
    (net (code "168") (name "unconnected-(JM1-Pad68)") (class "Default")
      (node (ref "JM1") (pin "68") (pinfunction "68_68") (pintype "passive"))
    )
    (net (code "169") (name "unconnected-(JM1-Pad70)") (class "Default")
      (node (ref "JM1") (pin "70") (pinfunction "70_70") (pintype "passive"))
    )
    (net (code "170") (name "unconnected-(JM1-Pad72)") (class "Default")
      (node (ref "JM1") (pin "72") (pinfunction "72_72") (pintype "passive"))
    )
    (net (code "171") (name "unconnected-(JM1-Pad75)") (class "Default")
      (node (ref "JM1") (pin "75") (pinfunction "75_75") (pintype "passive"))
    )
    (net (code "172") (name "unconnected-(JM1-Pad77)") (class "Default")
      (node (ref "JM1") (pin "77") (pinfunction "77_77") (pintype "passive"))
    )
    (net (code "173") (name "unconnected-(JM1-Pad80)") (class "Default")
      (node (ref "JM1") (pin "80") (pinfunction "80_80") (pintype "passive"))
    )
    (net (code "174") (name "unconnected-(JM1-Pad82)") (class "Default")
      (node (ref "JM1") (pin "82") (pinfunction "82_82") (pintype "passive"))
    )
    (net (code "175") (name "unconnected-(JM1-Pad84)") (class "Default")
      (node (ref "JM1") (pin "84") (pinfunction "84_84") (pintype "passive"))
    )
    (net (code "176") (name "unconnected-(JM1-Pad86)") (class "Default")
      (node (ref "JM1") (pin "86") (pinfunction "86_86") (pintype "passive"))
    )
    (net (code "177") (name "unconnected-(JM1-Pad88)") (class "Default")
      (node (ref "JM1") (pin "88") (pinfunction "88_88") (pintype "passive"))
    )
    (net (code "178") (name "unconnected-(JM1-Pad90)") (class "Default")
      (node (ref "JM1") (pin "90") (pinfunction "90_90") (pintype "passive"))
    )
    (net (code "179") (name "unconnected-(JM1-Pad91)") (class "Default")
      (node (ref "JM1") (pin "91") (pinfunction "91_91") (pintype "passive"))
    )
    (net (code "180") (name "unconnected-(JM1-Pad92)") (class "Default")
      (node (ref "JM1") (pin "92") (pinfunction "92_92") (pintype "passive"))
    )
    (net (code "181") (name "unconnected-(JM1-Pad98)") (class "Default")
      (node (ref "JM1") (pin "98") (pinfunction "98_98") (pintype "passive"))
    )
    (net (code "182") (name "unconnected-(JM1-Pad100)") (class "Default")
      (node (ref "JM1") (pin "100") (pinfunction "100_100") (pintype "passive"))
    )
    (net (code "183") (name "unconnected-(JM2-Pad6)") (class "Default")
      (node (ref "JM2") (pin "6") (pinfunction "6_6") (pintype "passive+no_connect"))
    )
    (net (code "184") (name "unconnected-(JM2-Pad9)") (class "Default")
      (node (ref "JM2") (pin "9") (pinfunction "9_9") (pintype "passive"))
    )
    (net (code "185") (name "unconnected-(JM2-Pad11)") (class "Default")
      (node (ref "JM2") (pin "11") (pinfunction "11_11") (pintype "passive"))
    )
    (net (code "186") (name "unconnected-(JM2-Pad12)") (class "Default")
      (node (ref "JM2") (pin "12") (pinfunction "12_12") (pintype "passive"))
    )
    (net (code "187") (name "unconnected-(JM2-Pad13)") (class "Default")
      (node (ref "JM2") (pin "13") (pinfunction "13_13") (pintype "passive"))
    )
    (net (code "188") (name "unconnected-(JM2-Pad14)") (class "Default")
      (node (ref "JM2") (pin "14") (pinfunction "14_14") (pintype "passive"))
    )
    (net (code "189") (name "unconnected-(JM2-Pad15)") (class "Default")
      (node (ref "JM2") (pin "15") (pinfunction "15_15") (pintype "passive"))
    )
    (net (code "190") (name "unconnected-(JM2-Pad16)") (class "Default")
      (node (ref "JM2") (pin "16") (pinfunction "16_16") (pintype "passive"))
    )
    (net (code "191") (name "unconnected-(JM2-Pad17)") (class "Default")
      (node (ref "JM2") (pin "17") (pinfunction "17_17") (pintype "passive"))
    )
    (net (code "192") (name "unconnected-(JM2-Pad18)") (class "Default")
      (node (ref "JM2") (pin "18") (pinfunction "18_18") (pintype "passive"))
    )
    (net (code "193") (name "unconnected-(JM2-Pad20)") (class "Default")
      (node (ref "JM2") (pin "20") (pinfunction "20_20") (pintype "passive"))
    )
    (net (code "194") (name "unconnected-(JM2-Pad21)") (class "Default")
      (node (ref "JM2") (pin "21") (pinfunction "21_21") (pintype "passive"))
    )
    (net (code "195") (name "unconnected-(JM2-Pad22)") (class "Default")
      (node (ref "JM2") (pin "22") (pinfunction "22_22") (pintype "passive"))
    )
    (net (code "196") (name "unconnected-(JM2-Pad23)") (class "Default")
      (node (ref "JM2") (pin "23") (pinfunction "23_23") (pintype "passive"))
    )
    (net (code "197") (name "unconnected-(JM2-Pad24)") (class "Default")
      (node (ref "JM2") (pin "24") (pinfunction "24_24") (pintype "passive"))
    )
    (net (code "198") (name "unconnected-(JM2-Pad25)") (class "Default")
      (node (ref "JM2") (pin "25") (pinfunction "25_25") (pintype "passive"))
    )
    (net (code "199") (name "unconnected-(JM2-Pad26)") (class "Default")
      (node (ref "JM2") (pin "26") (pinfunction "26_26") (pintype "passive"))
    )
    (net (code "200") (name "unconnected-(JM2-Pad27)") (class "Default")
      (node (ref "JM2") (pin "27") (pinfunction "27_27") (pintype "passive"))
    )
    (net (code "201") (name "unconnected-(JM2-Pad28)") (class "Default")
      (node (ref "JM2") (pin "28") (pinfunction "28_28") (pintype "passive"))
    )
    (net (code "202") (name "unconnected-(JM2-Pad30)") (class "Default")
      (node (ref "JM2") (pin "30") (pinfunction "30_30") (pintype "passive+no_connect"))
    )
    (net (code "203") (name "unconnected-(JM2-Pad32)") (class "Default")
      (node (ref "JM2") (pin "32") (pinfunction "32_32") (pintype "passive"))
    )
    (net (code "204") (name "unconnected-(JM2-Pad34)") (class "Default")
      (node (ref "JM2") (pin "34") (pinfunction "34_34") (pintype "passive"))
    )
    (net (code "205") (name "unconnected-(JM2-Pad36)") (class "Default")
      (node (ref "JM2") (pin "36") (pinfunction "36_36") (pintype "passive"))
    )
    (net (code "206") (name "unconnected-(JM2-Pad38)") (class "Default")
      (node (ref "JM2") (pin "38") (pinfunction "38_38") (pintype "passive"))
    )
    (net (code "207") (name "unconnected-(JM2-Pad46)") (class "Default")
      (node (ref "JM2") (pin "46") (pinfunction "46_46") (pintype "passive+no_connect"))
    )
    (net (code "208") (name "unconnected-(JM2-Pad67)") (class "Default")
      (node (ref "JM2") (pin "67") (pinfunction "67_67") (pintype "passive"))
    )
    (net (code "209") (name "unconnected-(JM2-Pad71)") (class "Default")
      (node (ref "JM2") (pin "71") (pinfunction "71_71") (pintype "passive"))
    )
    (net (code "210") (name "unconnected-(JM2-Pad72)") (class "Default")
      (node (ref "JM2") (pin "72") (pinfunction "72_72") (pintype "passive"))
    )
    (net (code "211") (name "unconnected-(JM2-Pad73)") (class "Default")
      (node (ref "JM2") (pin "73") (pinfunction "73_73") (pintype "passive"))
    )
    (net (code "212") (name "unconnected-(JM2-Pad74)") (class "Default")
      (node (ref "JM2") (pin "74") (pinfunction "74_74") (pintype "passive"))
    )
    (net (code "213") (name "unconnected-(JM2-Pad75)") (class "Default")
      (node (ref "JM2") (pin "75") (pinfunction "75_75") (pintype "passive"))
    )
    (net (code "214") (name "unconnected-(JM2-Pad76)") (class "Default")
      (node (ref "JM2") (pin "76") (pinfunction "76_76") (pintype "passive"))
    )
    (net (code "215") (name "unconnected-(JM2-Pad77)") (class "Default")
      (node (ref "JM2") (pin "77") (pinfunction "77_77") (pintype "passive"))
    )
    (net (code "216") (name "unconnected-(JM2-Pad78)") (class "Default")
      (node (ref "JM2") (pin "78") (pinfunction "78_78") (pintype "passive"))
    )
    (net (code "217") (name "unconnected-(JM2-Pad81)") (class "Default")
      (node (ref "JM2") (pin "81") (pinfunction "81_81") (pintype "passive"))
    )
    (net (code "218") (name "unconnected-(JM2-Pad82)") (class "Default")
      (node (ref "JM2") (pin "82") (pinfunction "82_82") (pintype "passive"))
    )
    (net (code "219") (name "unconnected-(JM2-Pad83)") (class "Default")
      (node (ref "JM2") (pin "83") (pinfunction "83_83") (pintype "passive"))
    )
    (net (code "220") (name "unconnected-(JM2-Pad84)") (class "Default")
      (node (ref "JM2") (pin "84") (pinfunction "84_84") (pintype "passive"))
    )
    (net (code "221") (name "unconnected-(JM2-Pad85)") (class "Default")
      (node (ref "JM2") (pin "85") (pinfunction "85_85") (pintype "passive"))
    )
    (net (code "222") (name "unconnected-(JM2-Pad86)") (class "Default")
      (node (ref "JM2") (pin "86") (pinfunction "86_86") (pintype "passive"))
    )
    (net (code "223") (name "unconnected-(JM2-Pad87)") (class "Default")
      (node (ref "JM2") (pin "87") (pinfunction "87_87") (pintype "passive"))
    )
    (net (code "224") (name "unconnected-(JM2-Pad88)") (class "Default")
      (node (ref "JM2") (pin "88") (pinfunction "88_88") (pintype "passive"))
    )
    (net (code "225") (name "unconnected-(JM2-Pad90)") (class "Default")
      (node (ref "JM2") (pin "90") (pinfunction "90_90") (pintype "passive"))
    )
    (net (code "226") (name "unconnected-(JM2-Pad91)") (class "Default")
      (node (ref "JM2") (pin "91") (pinfunction "91_91") (pintype "passive"))
    )
    (net (code "227") (name "unconnected-(JM2-Pad93)") (class "Default")
      (node (ref "JM2") (pin "93") (pinfunction "93_93") (pintype "passive"))
    )
    (net (code "228") (name "unconnected-(JM2-Pad95)") (class "Default")
      (node (ref "JM2") (pin "95") (pinfunction "95_95") (pintype "passive"))
    )
    (net (code "229") (name "unconnected-(JM2-Pad97)") (class "Default")
      (node (ref "JM2") (pin "97") (pinfunction "97_97") (pintype "passive"))
    )
    (net (code "230") (name "unconnected-(JM2-Pad99)") (class "Default")
      (node (ref "JM2") (pin "99") (pinfunction "99_99") (pintype "passive"))
    )
    (net (code "231") (name "unconnected-(JM3-Pad1)") (class "Default")
      (node (ref "JM3") (pin "1") (pinfunction "1_1") (pintype "passive"))
    )
    (net (code "232") (name "unconnected-(JM3-Pad2)") (class "Default")
      (node (ref "JM3") (pin "2") (pinfunction "2_2") (pintype "passive"))
    )
    (net (code "233") (name "unconnected-(JM3-Pad3)") (class "Default")
      (node (ref "JM3") (pin "3") (pinfunction "3_3") (pintype "passive"))
    )
    (net (code "234") (name "unconnected-(JM3-Pad4)") (class "Default")
      (node (ref "JM3") (pin "4") (pinfunction "4_4") (pintype "passive"))
    )
    (net (code "235") (name "unconnected-(JM3-Pad31)") (class "Default")
      (node (ref "JM3") (pin "31") (pinfunction "31_31") (pintype "passive"))
    )
    (net (code "236") (name "unconnected-(JM3-Pad33)") (class "Default")
      (node (ref "JM3") (pin "33") (pinfunction "33_33") (pintype "passive"))
    )
    (net (code "237") (name "unconnected-(JM3-Pad37)") (class "Default")
      (node (ref "JM3") (pin "37") (pinfunction "37_37") (pintype "passive"))
    )
    (net (code "238") (name "unconnected-(JM3-Pad38)") (class "Default")
      (node (ref "JM3") (pin "38") (pinfunction "38_38") (pintype "passive"))
    )
    (net (code "239") (name "unconnected-(JM3-Pad39)") (class "Default")
      (node (ref "JM3") (pin "39") (pinfunction "39_39") (pintype "passive"))
    )
    (net (code "240") (name "unconnected-(JM3-Pad40)") (class "Default")
      (node (ref "JM3") (pin "40") (pinfunction "40_40") (pintype "passive"))
    )
    (net (code "241") (name "unconnected-(JM3-Pad41)") (class "Default")
      (node (ref "JM3") (pin "41") (pinfunction "41_41") (pintype "passive"))
    )
    (net (code "242") (name "unconnected-(JM3-Pad42)") (class "Default")
      (node (ref "JM3") (pin "42") (pinfunction "42_42") (pintype "passive"))
    )
    (net (code "243") (name "unconnected-(JM3-Pad43)") (class "Default")
      (node (ref "JM3") (pin "43") (pinfunction "43_43") (pintype "passive"))
    )
    (net (code "244") (name "unconnected-(JM3-Pad44)") (class "Default")
      (node (ref "JM3") (pin "44") (pinfunction "44_44") (pintype "passive"))
    )
    (net (code "245") (name "unconnected-(JM3-Pad47)") (class "Default")
      (node (ref "JM3") (pin "47") (pinfunction "47_47") (pintype "passive"))
    )
    (net (code "246") (name "unconnected-(JM3-Pad48)") (class "Default")
      (node (ref "JM3") (pin "48") (pinfunction "48_48") (pintype "passive"))
    )
    (net (code "247") (name "unconnected-(JM3-Pad49)") (class "Default")
      (node (ref "JM3") (pin "49") (pinfunction "49_49") (pintype "passive"))
    )
    (net (code "248") (name "unconnected-(JM3-Pad50)") (class "Default")
      (node (ref "JM3") (pin "50") (pinfunction "50_50") (pintype "passive"))
    )
    (net (code "249") (name "unconnected-(JM3-Pad51)") (class "Default")
      (node (ref "JM3") (pin "51") (pinfunction "51_51") (pintype "passive"))
    )
    (net (code "250") (name "unconnected-(JM3-Pad52)") (class "Default")
      (node (ref "JM3") (pin "52") (pinfunction "52_52") (pintype "passive"))
    )
    (net (code "251") (name "unconnected-(JM3-Pad53)") (class "Default")
      (node (ref "JM3") (pin "53") (pinfunction "53_53") (pintype "passive"))
    )
    (net (code "252") (name "unconnected-(JM3-Pad54)") (class "Default")
      (node (ref "JM3") (pin "54") (pinfunction "54_54") (pintype "passive"))
    )
    (net (code "253") (name "unconnected-(JM3-Pad55)") (class "Default")
      (node (ref "JM3") (pin "55") (pinfunction "55_55") (pintype "passive"))
    )
    (net (code "254") (name "unconnected-(JM3-Pad56)") (class "Default")
      (node (ref "JM3") (pin "56") (pinfunction "56_56") (pintype "passive"))
    )
    (net (code "255") (name "unconnected-(JM3-Pad57)") (class "Default")
      (node (ref "JM3") (pin "57") (pinfunction "57_57") (pintype "passive"))
    )
    (net (code "256") (name "unconnected-(JM3-Pad58)") (class "Default")
      (node (ref "JM3") (pin "58") (pinfunction "58_58") (pintype "passive"))
    )
    (net (code "257") (name "unconnected-(JM3-Pad59)") (class "Default")
      (node (ref "JM3") (pin "59") (pinfunction "59_59") (pintype "passive"))
    )
  )
)
